# SwrMetter.net
KiCad netlist of a schematic drawn in EAGLE
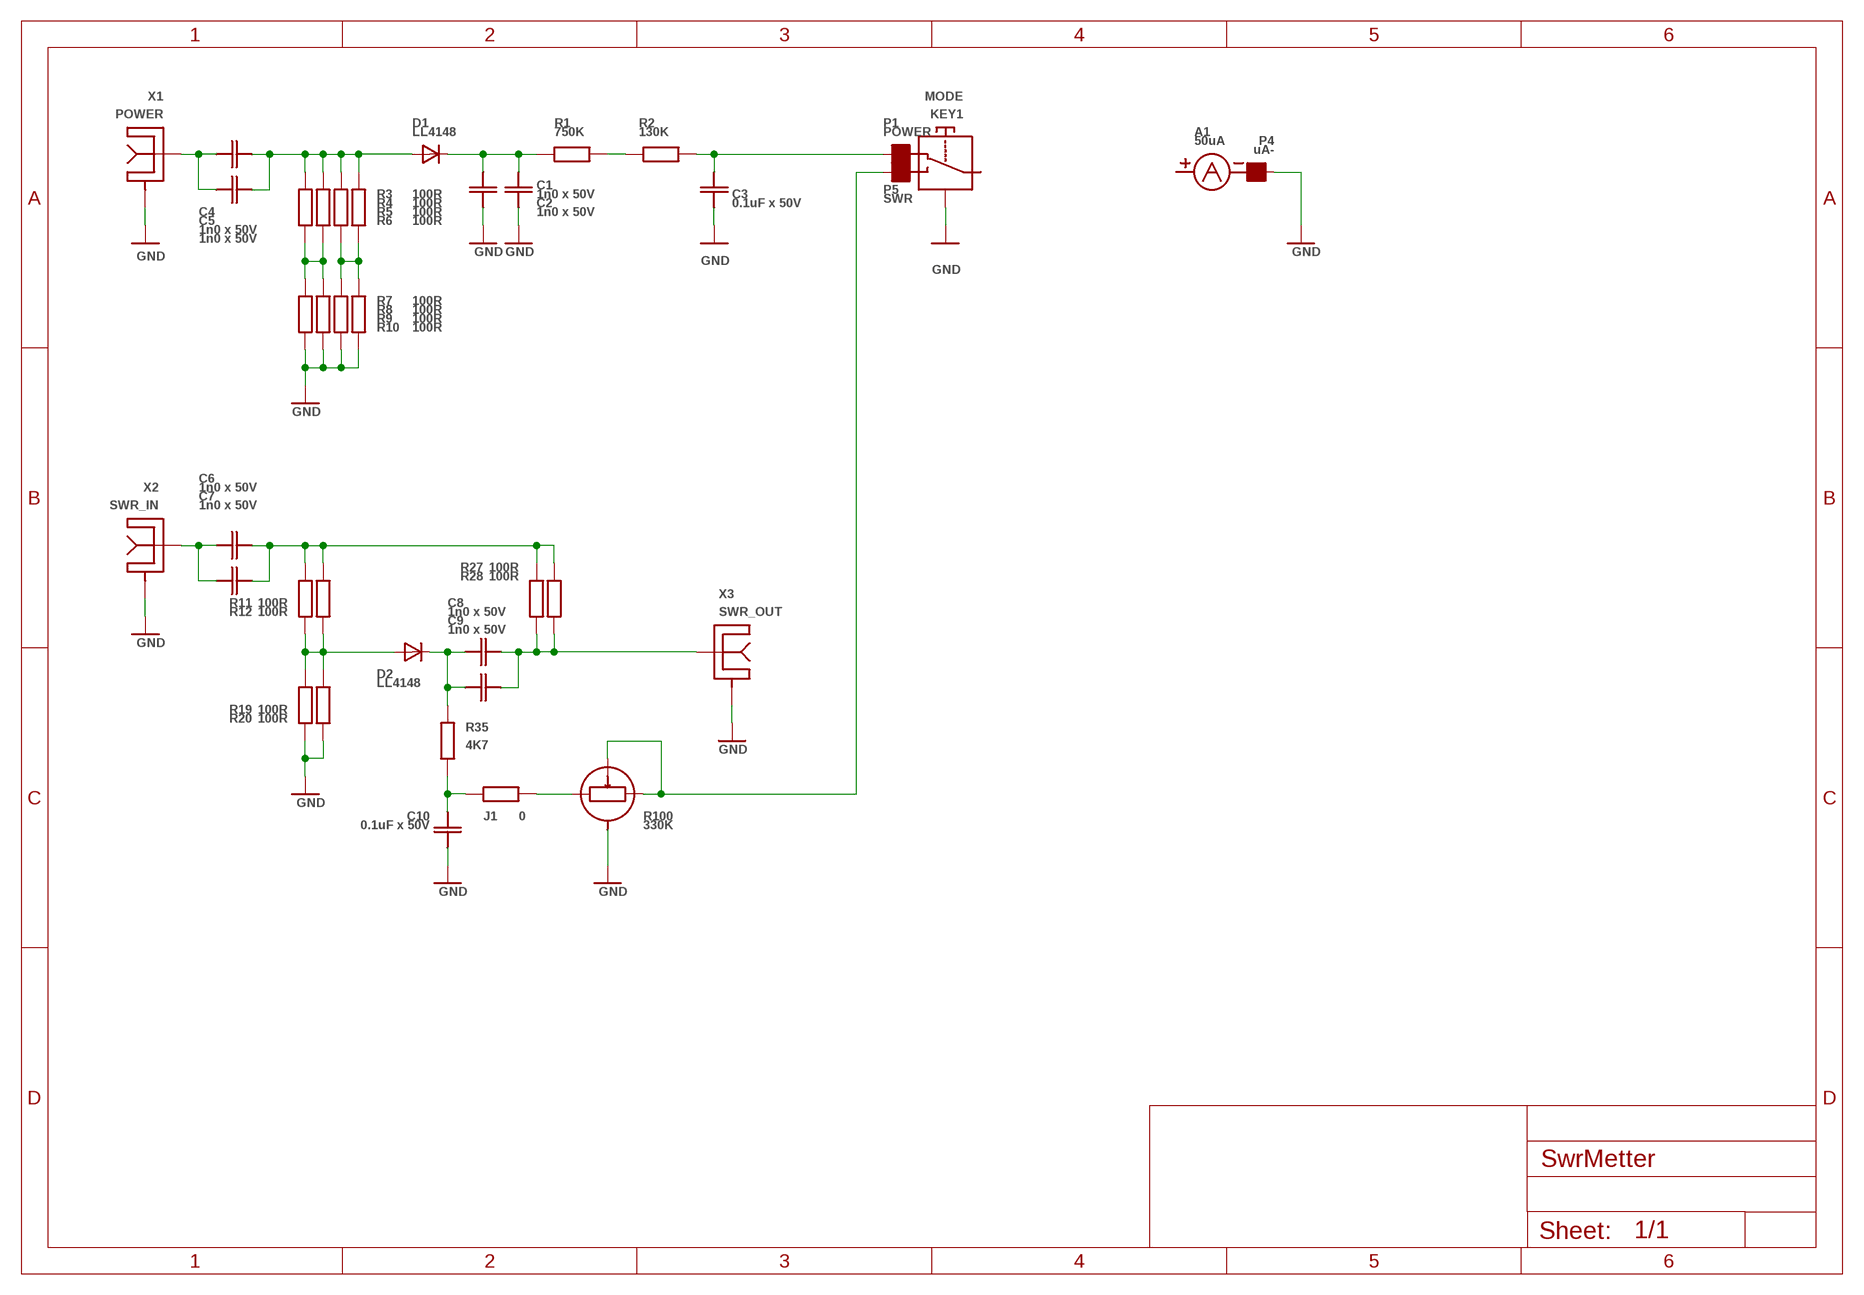
[diagram p0: schematic, sheet 1]

(export (version "E")
  (design (tool "Eeschema 10.0.6"))
  (components
    (comp (ref "A1")
      (value "50uA")
      (footprint "eagle-import:MICRO_AMPMET(UNKNOWN)")
      (libsource (lib "eagle-import") (part "AMPERMETER_NO_PIN(CHINA_MICRO_AMPM)"))
    )
    (comp (ref "C1")
      (value "1n0 x 50V")
      (footprint "eagle-import:RSMD_1206")
      (libsource (lib "eagle-import") (part "CSMD_1206"))
    )
    (comp (ref "C2")
      (value "1n0 x 50V")
      (footprint "eagle-import:RSMD_1206")
      (libsource (lib "eagle-import") (part "CSMD_1206"))
    )
    (comp (ref "C3")
      (value "0.1uF x 50V")
      (footprint "eagle-import:RSMD_1206")
      (libsource (lib "eagle-import") (part "CSMD_1206"))
    )
    (comp (ref "C4")
      (value "1n0 x 50V")
      (footprint "eagle-import:RSMD_1206")
      (libsource (lib "eagle-import") (part "CSMD_1206"))
    )
    (comp (ref "C5")
      (value "1n0 x 50V")
      (footprint "eagle-import:RSMD_1206")
      (libsource (lib "eagle-import") (part "CSMD_1206"))
    )
    (comp (ref "C6")
      (value "1n0 x 50V")
      (footprint "eagle-import:RSMD_1206")
      (libsource (lib "eagle-import") (part "CSMD_1206"))
    )
    (comp (ref "C7")
      (value "1n0 x 50V")
      (footprint "eagle-import:RSMD_1206")
      (libsource (lib "eagle-import") (part "CSMD_1206"))
    )
    (comp (ref "C8")
      (value "1n0 x 50V")
      (footprint "eagle-import:RSMD_1206")
      (libsource (lib "eagle-import") (part "CSMD_1206"))
    )
    (comp (ref "C9")
      (value "1n0 x 50V")
      (footprint "eagle-import:RSMD_1206")
      (libsource (lib "eagle-import") (part "CSMD_1206"))
    )
    (comp (ref "C10")
      (value "0.1uF x 50V")
      (footprint "eagle-import:RSMD_1206")
      (libsource (lib "eagle-import") (part "CSMD_1206"))
    )
    (comp (ref "D1")
      (value "LL4148")
      (footprint "eagle-import:SOD-80")
      (libsource (lib "eagle-import") (part "LL4147SOD-80"))
    )
    (comp (ref "D2")
      (value "LL4148")
      (footprint "eagle-import:SOD-80")
      (libsource (lib "eagle-import") (part "LL4147SOD-80"))
    )
    (comp (ref "J1")
      (value "0")
      (footprint "eagle-import:RSMD_2512")
      (libsource (lib "eagle-import") (part "RSMD_2512"))
    )
    (comp (ref "KEY1")
      (value "MODE")
      (footprint "eagle-import:KEY_MTS1_NO_PINS")
      (libsource (lib "eagle-import") (part "KEY_2POS_NO_PINSMTS1"))
    )
    (comp (ref "P1")
      (value "POWER")
      (footprint "eagle-import:PAD_4X4")
      (libsource (lib "eagle-import") (part "PADPAD_4X4"))
    )
    (comp (ref "P4")
      (value "uA-")
      (footprint "eagle-import:PAD_4X4")
      (libsource (lib "eagle-import") (part "PADPAD_4X4"))
    )
    (comp (ref "P5")
      (value "SWR")
      (footprint "eagle-import:PAD_4X4")
      (libsource (lib "eagle-import") (part "PADPAD_4X4"))
    )
    (comp (ref "R1")
      (value "750K")
      (footprint "eagle-import:RSMD_1206")
      (libsource (lib "eagle-import") (part "RSMD_1206"))
    )
    (comp (ref "R2")
      (value "130K")
      (footprint "eagle-import:RSMD_1206")
      (libsource (lib "eagle-import") (part "RSMD_1206"))
    )
    (comp (ref "R3")
      (value "100R")
      (footprint "eagle-import:RSMD_2512")
      (libsource (lib "eagle-import") (part "RSMD_2512"))
    )
    (comp (ref "R4")
      (value "100R")
      (footprint "eagle-import:RSMD_2512")
      (libsource (lib "eagle-import") (part "RSMD_2512"))
    )
    (comp (ref "R5")
      (value "100R")
      (footprint "eagle-import:RSMD_2512")
      (libsource (lib "eagle-import") (part "RSMD_2512"))
    )
    (comp (ref "R6")
      (value "100R")
      (footprint "eagle-import:RSMD_2512")
      (libsource (lib "eagle-import") (part "RSMD_2512"))
    )
    (comp (ref "R7")
      (value "100R")
      (footprint "eagle-import:RSMD_2512")
      (libsource (lib "eagle-import") (part "RSMD_2512"))
    )
    (comp (ref "R8")
      (value "100R")
      (footprint "eagle-import:RSMD_2512")
      (libsource (lib "eagle-import") (part "RSMD_2512"))
    )
    (comp (ref "R9")
      (value "100R")
      (footprint "eagle-import:RSMD_2512")
      (libsource (lib "eagle-import") (part "RSMD_2512"))
    )
    (comp (ref "R10")
      (value "100R")
      (footprint "eagle-import:RSMD_2512")
      (libsource (lib "eagle-import") (part "RSMD_2512"))
    )
    (comp (ref "R11")
      (value "100R")
      (footprint "eagle-import:RSMD_2512")
      (libsource (lib "eagle-import") (part "RSMD_2512"))
    )
    (comp (ref "R12")
      (value "100R")
      (footprint "eagle-import:RSMD_2512")
      (libsource (lib "eagle-import") (part "RSMD_2512"))
    )
    (comp (ref "R19")
      (value "100R")
      (footprint "eagle-import:RSMD_2512")
      (libsource (lib "eagle-import") (part "RSMD_2512"))
    )
    (comp (ref "R20")
      (value "100R")
      (footprint "eagle-import:RSMD_2512")
      (libsource (lib "eagle-import") (part "RSMD_2512"))
    )
    (comp (ref "R27")
      (value "100R")
      (footprint "eagle-import:RSMD_2512")
      (libsource (lib "eagle-import") (part "RSMD_2512"))
    )
    (comp (ref "R28")
      (value "100R")
      (footprint "eagle-import:RSMD_2512")
      (libsource (lib "eagle-import") (part "RSMD_2512"))
    )
    (comp (ref "R35")
      (value "4K7")
      (footprint "eagle-import:RSMD_0805")
      (libsource (lib "eagle-import") (part "RSMD_0805"))
    )
    (comp (ref "R100")
      (value "330K")
      (footprint "eagle-import:SP3-4AM")
      (libsource (lib "eagle-import") (part "R_ADJ_WITH_SHIELDSP4-AM"))
    )
    (comp (ref "X1")
      (value "POWER")
      (footprint "eagle-import:PL-239(FEMALE)")
      (libsource (lib "eagle-import") (part "PL239_FEM4SCREWS"))
    )
    (comp (ref "X2")
      (value "SWR_IN")
      (footprint "eagle-import:PL-239(FEMALE)")
      (libsource (lib "eagle-import") (part "PL239_FEM4SCREWS"))
    )
    (comp (ref "X3")
      (value "SWR_OUT")
      (footprint "eagle-import:PL-239(FEMALE)")
      (libsource (lib "eagle-import") (part "PL239_FEM4SCREWS"))
    )
  )
  (nets
    (net (code "1") (name "GND") (class "Default")
      (node (ref "C1") (pin "PAD_0") (pinfunction "PIN0_PAD_0") (pintype "bidirectional"))
      (node (ref "C10") (pin "PAD_1") (pinfunction "PIN1_PAD_1") (pintype "bidirectional"))
      (node (ref "C2") (pin "PAD_0") (pinfunction "PIN0_PAD_0") (pintype "bidirectional"))
      (node (ref "C3") (pin "PAD_0") (pinfunction "PIN0_PAD_0") (pintype "bidirectional"))
      (node (ref "KEY1") (pin "GND1") (pinfunction "PACKAGE_GND1") (pintype "bidirectional"))
      (node (ref "KEY1") (pin "GND2") (pinfunction "PACKAGE_GND2") (pintype "bidirectional"))
      (node (ref "P4") (pin "PAD") (pinfunction "PIN1_PAD") (pintype "bidirectional"))
      (node (ref "R10") (pin "PAD0") (pinfunction "PIN0_PAD0") (pintype "passive"))
      (node (ref "R100") (pin "PACKAGE1") (pinfunction "PACKAGE_PACKAGE1") (pintype "bidirectional"))
      (node (ref "R100") (pin "PACKAGE2") (pinfunction "PACKAGE_PACKAGE2") (pintype "bidirectional"))
      (node (ref "R19") (pin "PAD0") (pinfunction "PIN0_PAD0") (pintype "passive"))
      (node (ref "R20") (pin "PAD0") (pinfunction "PIN0_PAD0") (pintype "passive"))
      (node (ref "R7") (pin "PAD0") (pinfunction "PIN0_PAD0") (pintype "passive"))
      (node (ref "R8") (pin "PAD0") (pinfunction "PIN0_PAD0") (pintype "passive"))
      (node (ref "R9") (pin "PAD0") (pinfunction "PIN0_PAD0") (pintype "passive"))
      (node (ref "X1") (pin "CENTER_DRILL") (pinfunction "GND_CENTER_DRILL") (pintype "bidirectional"))
      (node (ref "X1") (pin "SCREW1") (pinfunction "GND_SCREW1") (pintype "bidirectional"))
      (node (ref "X1") (pin "SCREW2") (pinfunction "GND_SCREW2") (pintype "bidirectional"))
      (node (ref "X1") (pin "SCREW3") (pinfunction "GND_SCREW3") (pintype "bidirectional"))
      (node (ref "X1") (pin "SCREW4") (pinfunction "GND_SCREW4") (pintype "bidirectional"))
      (node (ref "X2") (pin "CENTER_DRILL") (pinfunction "GND_CENTER_DRILL") (pintype "bidirectional"))
      (node (ref "X2") (pin "SCREW1") (pinfunction "GND_SCREW1") (pintype "bidirectional"))
      (node (ref "X2") (pin "SCREW2") (pinfunction "GND_SCREW2") (pintype "bidirectional"))
      (node (ref "X2") (pin "SCREW3") (pinfunction "GND_SCREW3") (pintype "bidirectional"))
      (node (ref "X2") (pin "SCREW4") (pinfunction "GND_SCREW4") (pintype "bidirectional"))
      (node (ref "X3") (pin "CENTER_DRILL") (pinfunction "GND_CENTER_DRILL") (pintype "bidirectional"))
      (node (ref "X3") (pin "SCREW1") (pinfunction "GND_SCREW1") (pintype "bidirectional"))
      (node (ref "X3") (pin "SCREW2") (pinfunction "GND_SCREW2") (pintype "bidirectional"))
      (node (ref "X3") (pin "SCREW3") (pinfunction "GND_SCREW3") (pintype "bidirectional"))
      (node (ref "X3") (pin "SCREW4") (pinfunction "GND_SCREW4") (pintype "bidirectional"))
    )
    (net (code "2") (name "Net-(C1-PIN1)") (class "Default")
      (node (ref "C1") (pin "PAD_1") (pinfunction "PIN1_PAD_1") (pintype "bidirectional"))
      (node (ref "C2") (pin "PAD_1") (pinfunction "PIN1_PAD_1") (pintype "bidirectional"))
      (node (ref "D1") (pin "CATHODE") (pinfunction "CATHODE_CATHODE") (pintype "passive"))
      (node (ref "R1") (pin "PAD_1") (pinfunction "PIN1_PAD_1") (pintype "passive"))
    )
    (net (code "3") (name "Net-(C3-PIN1)") (class "Default")
      (node (ref "C3") (pin "PAD_1") (pinfunction "PIN1_PAD_1") (pintype "bidirectional"))
      (node (ref "P1") (pin "PAD") (pinfunction "PIN1_PAD") (pintype "bidirectional"))
      (node (ref "R2") (pin "PAD_0") (pinfunction "PIN0_PAD_0") (pintype "passive"))
    )
    (net (code "4") (name "Net-(C4-PIN0)") (class "Default")
      (node (ref "C4") (pin "PAD_0") (pinfunction "PIN0_PAD_0") (pintype "bidirectional"))
      (node (ref "C5") (pin "PAD_0") (pinfunction "PIN0_PAD_0") (pintype "bidirectional"))
      (node (ref "D1") (pin "ANODE") (pinfunction "ANODE_ANODE") (pintype "passive"))
      (node (ref "R3") (pin "PAD1") (pinfunction "PIN1_PAD1") (pintype "passive"))
      (node (ref "R4") (pin "PAD1") (pinfunction "PIN1_PAD1") (pintype "passive"))
      (node (ref "R5") (pin "PAD1") (pinfunction "PIN1_PAD1") (pintype "passive"))
      (node (ref "R6") (pin "PAD1") (pinfunction "PIN1_PAD1") (pintype "passive"))
    )
    (net (code "5") (name "Net-(C4-PIN1)") (class "Default")
      (node (ref "C4") (pin "PAD_1") (pinfunction "PIN1_PAD_1") (pintype "bidirectional"))
      (node (ref "C5") (pin "PAD_1") (pinfunction "PIN1_PAD_1") (pintype "bidirectional"))
      (node (ref "X1") (pin "SIGNAL") (pinfunction "SIGNAL_SIGNAL") (pintype "bidirectional"))
    )
    (net (code "6") (name "Net-(C6-PIN0)") (class "Default")
      (node (ref "C6") (pin "PAD_0") (pinfunction "PIN0_PAD_0") (pintype "bidirectional"))
      (node (ref "C7") (pin "PAD_0") (pinfunction "PIN0_PAD_0") (pintype "bidirectional"))
      (node (ref "R11") (pin "PAD1") (pinfunction "PIN1_PAD1") (pintype "passive"))
      (node (ref "R12") (pin "PAD1") (pinfunction "PIN1_PAD1") (pintype "passive"))
      (node (ref "R27") (pin "PAD1") (pinfunction "PIN1_PAD1") (pintype "passive"))
      (node (ref "R28") (pin "PAD1") (pinfunction "PIN1_PAD1") (pintype "passive"))
    )
    (net (code "7") (name "Net-(C6-PIN1)") (class "Default")
      (node (ref "C6") (pin "PAD_1") (pinfunction "PIN1_PAD_1") (pintype "bidirectional"))
      (node (ref "C7") (pin "PAD_1") (pinfunction "PIN1_PAD_1") (pintype "bidirectional"))
      (node (ref "X2") (pin "SIGNAL") (pinfunction "SIGNAL_SIGNAL") (pintype "bidirectional"))
    )
    (net (code "8") (name "Net-(C8-PIN0)") (class "Default")
      (node (ref "C8") (pin "PAD_0") (pinfunction "PIN0_PAD_0") (pintype "bidirectional"))
      (node (ref "C9") (pin "PAD_0") (pinfunction "PIN0_PAD_0") (pintype "bidirectional"))
      (node (ref "R27") (pin "PAD0") (pinfunction "PIN0_PAD0") (pintype "passive"))
      (node (ref "R28") (pin "PAD0") (pinfunction "PIN0_PAD0") (pintype "passive"))
      (node (ref "X3") (pin "SIGNAL") (pinfunction "SIGNAL_SIGNAL") (pintype "bidirectional"))
    )
    (net (code "9") (name "Net-(C8-PIN1)") (class "Default")
      (node (ref "C8") (pin "PAD_1") (pinfunction "PIN1_PAD_1") (pintype "bidirectional"))
      (node (ref "C9") (pin "PAD_1") (pinfunction "PIN1_PAD_1") (pintype "bidirectional"))
      (node (ref "D2") (pin "CATHODE") (pinfunction "CATHODE_CATHODE") (pintype "passive"))
      (node (ref "R35") (pin "PAD_1") (pinfunction "PIN1_PAD_1") (pintype "passive"))
    )
    (net (code "10") (name "Net-(C10-PIN0)") (class "Default")
      (node (ref "C10") (pin "PAD_0") (pinfunction "PIN0_PAD_0") (pintype "bidirectional"))
      (node (ref "J1") (pin "PAD1") (pinfunction "PIN1_PAD1") (pintype "passive"))
      (node (ref "R35") (pin "PAD_0") (pinfunction "PIN0_PAD_0") (pintype "passive"))
    )
    (net (code "11") (name "Net-(J1-PIN0)") (class "Default")
      (node (ref "J1") (pin "PAD0") (pinfunction "PIN0_PAD0") (pintype "passive"))
      (node (ref "R100") (pin "END_A") (pinfunction "END_A_END_A") (pintype "passive"))
    )
    (net (code "12") (name "Net-(P5-PIN1)") (class "Default")
      (node (ref "P5") (pin "PAD") (pinfunction "PIN1_PAD") (pintype "bidirectional"))
      (node (ref "R100") (pin "END_B") (pinfunction "END_B_END_B") (pintype "passive"))
      (node (ref "R100") (pin "MIDDLE") (pinfunction "MIDDLE_MIDDLE") (pintype "passive"))
    )
    (net (code "13") (name "Net-(R1-PIN0)") (class "Default")
      (node (ref "R1") (pin "PAD_0") (pinfunction "PIN0_PAD_0") (pintype "passive"))
      (node (ref "R2") (pin "PAD_1") (pinfunction "PIN1_PAD_1") (pintype "passive"))
    )
    (net (code "14") (name "Net-(R3-PIN0)") (class "Default")
      (node (ref "R3") (pin "PAD0") (pinfunction "PIN0_PAD0") (pintype "passive"))
      (node (ref "R4") (pin "PAD0") (pinfunction "PIN0_PAD0") (pintype "passive"))
      (node (ref "R7") (pin "PAD1") (pinfunction "PIN1_PAD1") (pintype "passive"))
      (node (ref "R8") (pin "PAD1") (pinfunction "PIN1_PAD1") (pintype "passive"))
    )
    (net (code "15") (name "Net-(R10-PIN1)") (class "Default")
      (node (ref "R10") (pin "PAD1") (pinfunction "PIN1_PAD1") (pintype "passive"))
      (node (ref "R5") (pin "PAD0") (pinfunction "PIN0_PAD0") (pintype "passive"))
      (node (ref "R6") (pin "PAD0") (pinfunction "PIN0_PAD0") (pintype "passive"))
      (node (ref "R9") (pin "PAD1") (pinfunction "PIN1_PAD1") (pintype "passive"))
    )
    (net (code "16") (name "Net-(R11-PIN0)") (class "Default")
      (node (ref "D2") (pin "ANODE") (pinfunction "ANODE_ANODE") (pintype "passive"))
      (node (ref "R11") (pin "PAD0") (pinfunction "PIN0_PAD0") (pintype "passive"))
      (node (ref "R12") (pin "PAD0") (pinfunction "PIN0_PAD0") (pintype "passive"))
      (node (ref "R19") (pin "PAD1") (pinfunction "PIN1_PAD1") (pintype "passive"))
      (node (ref "R20") (pin "PAD1") (pinfunction "PIN1_PAD1") (pintype "passive"))
    )
  )
)
